# Power_supply_Bat_sense.net
KiCad netlist of a schematic drawn in Altium Designer
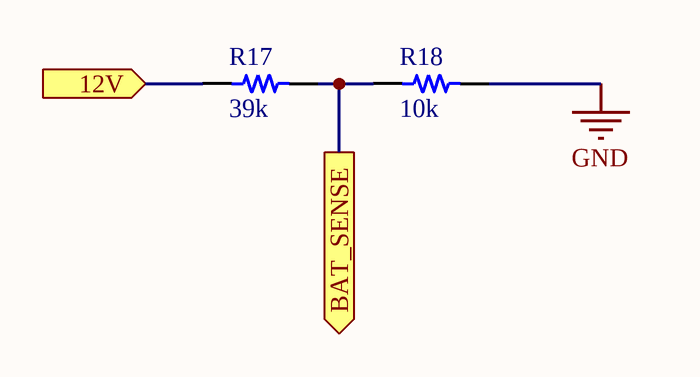
[diagram p0: Power_supply_Bat_sense.SchDoc]

(export (version "E")
  (design (tool "Eeschema 10.0.6"))
  (components
    (comp (ref "R17")
      (value "39k")
      (footprint "RES 0805/2012")
      (fields
        (field (name "TOLERANCE") "10%")
        (field (name "POWER") "1/10W")
        (field (name "Comment") "Resistor 39k 0805 1/10W 10%")
        (field (name "CREATED_BY") "Nick Mah")
      )
      (libsource (lib "Altium-Lib") (part "Resistor"))
    )
    (comp (ref "R18")
      (value "10k")
      (footprint "RES 0805/2012")
      (fields
        (field (name "TOLERANCE") "10%")
        (field (name "POWER") "1/4W")
        (field (name "Comment") "Resistor 10k 0805 1/4W 10%")
        (field (name "CREATED_BY") "Nick Mah")
      )
      (libsource (lib "Altium-Lib") (part "Resistor"))
    )
  )
  (nets
    (net (code "1") (name "/12V") (class "Default")
      (node (ref "R17") (pin "1") (pinfunction "1_1") (pintype "passive"))
    )
    (net (code "2") (name "/BAT_SENSE") (class "Default")
      (node (ref "R17") (pin "2") (pinfunction "2_2") (pintype "passive"))
      (node (ref "R18") (pin "1") (pinfunction "1_1") (pintype "passive"))
    )
    (net (code "3") (name "GND") (class "Default")
      (node (ref "R18") (pin "2") (pinfunction "2_2") (pintype "passive"))
    )
  )
)
